# -_-V3.net
KiCad netlist of a schematic drawn in Altium Designer
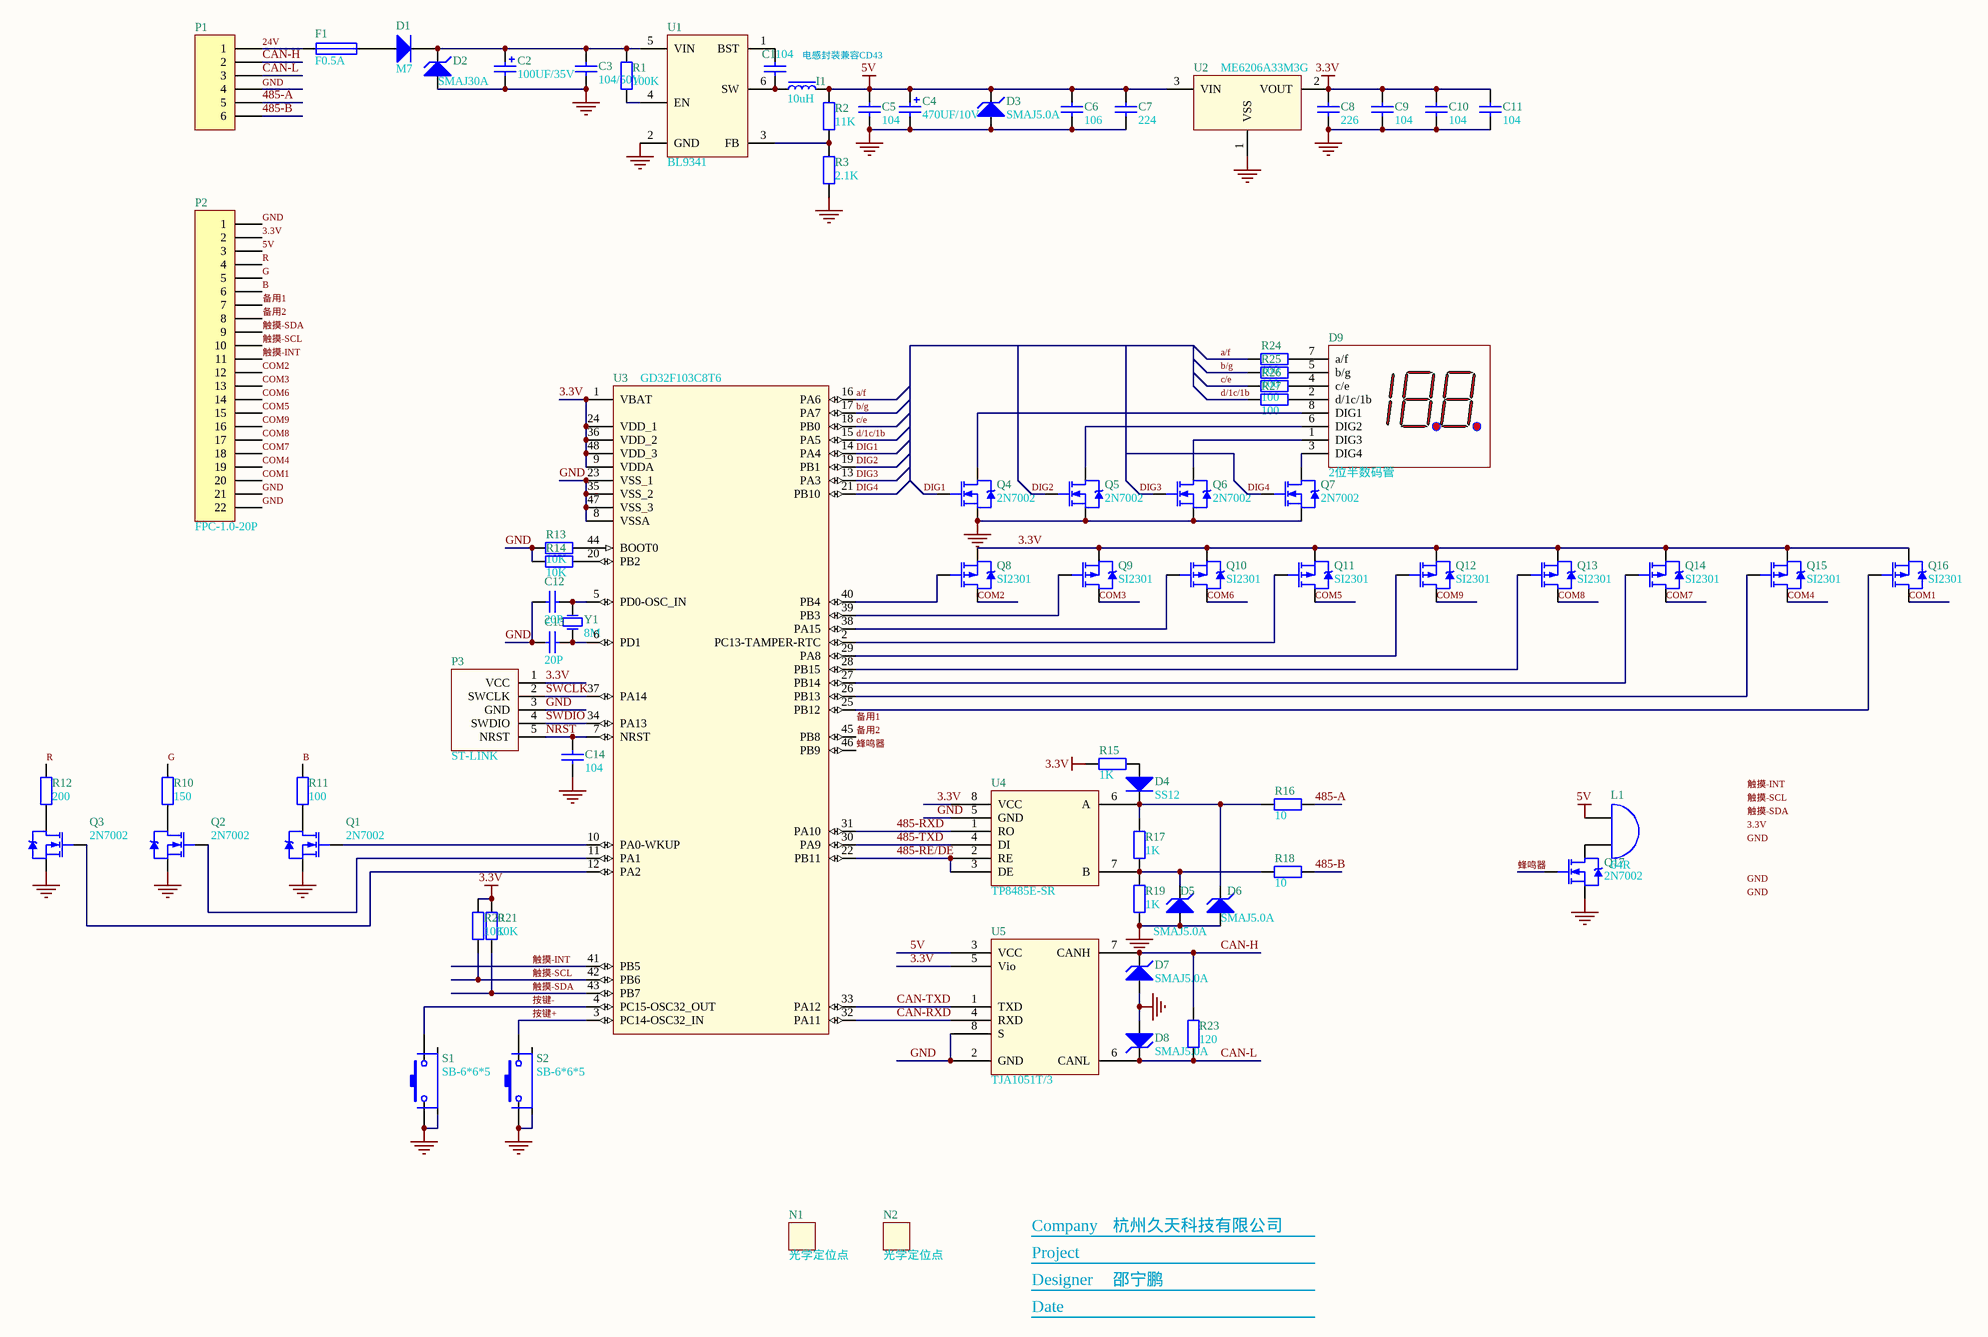
[diagram p0: 九键触摸面板-控制板-V3.SchDoc]

(export (version "E")
  (design (tool "Eeschema 10.0.6"))
  (components
    (comp (ref "C1")
      (value "104")
      (footprint "C-0603")
      (description "Capacitor")
      (fields (field (name "PUBLISHER") "Altium Limited"))
      (libsource (lib "元件2.0") (part "Cap"))
    )
    (comp (ref "C2")
      (value "100UF/35V")
      (footprint "贴片固态电容6.3*7.7")
      (description "Polarized Capacitor (Radial)")
      (fields (field (name "PUBLISHER") "Altium Limited"))
      (libsource (lib "元件2.0") (part "Cap Pol1"))
    )
    (comp (ref "C3")
      (value "104/50V")
      (footprint "C-0603")
      (description "Capacitor")
      (fields (field (name "PUBLISHER") "Altium Limited"))
      (libsource (lib "元件2.0") (part "Cap"))
    )
    (comp (ref "C4")
      (value "470UF/10V")
      (footprint "贴片固态电容6.3*7.7")
      (description "Polarized Capacitor (Radial)")
      (fields (field (name "PUBLISHER") "Altium Limited"))
      (libsource (lib "元件2.0") (part "Cap Pol1"))
    )
    (comp (ref "C5")
      (value "104")
      (footprint "C-0603")
      (description "Capacitor")
      (fields (field (name "PUBLISHER") "Altium Limited"))
      (libsource (lib "元件2.0") (part "Cap"))
    )
    (comp (ref "C6")
      (value "106")
      (footprint "C-0603")
      (description "Capacitor")
      (fields (field (name "PUBLISHER") "Altium Limited"))
      (libsource (lib "元件2.0") (part "Cap"))
    )
    (comp (ref "C7")
      (value "224")
      (footprint "C-0603")
      (description "Capacitor")
      (fields (field (name "PUBLISHER") "Altium Limited"))
      (libsource (lib "元件2.0") (part "Cap"))
    )
    (comp (ref "C8")
      (value "226")
      (footprint "C-0603")
      (description "Capacitor")
      (fields (field (name "PUBLISHER") "Altium Limited"))
      (libsource (lib "元件2.0") (part "Cap"))
    )
    (comp (ref "C9")
      (value "104")
      (footprint "C-0603")
      (description "Capacitor")
      (fields (field (name "PUBLISHER") "Altium Limited"))
      (libsource (lib "元件2.0") (part "Cap"))
    )
    (comp (ref "C10")
      (value "104")
      (footprint "C-0603")
      (description "Capacitor")
      (fields (field (name "PUBLISHER") "Altium Limited"))
      (libsource (lib "元件2.0") (part "Cap"))
    )
    (comp (ref "C11")
      (value "104")
      (footprint "C-0603")
      (description "Capacitor")
      (fields (field (name "PUBLISHER") "Altium Limited"))
      (libsource (lib "元件2.0") (part "Cap"))
    )
    (comp (ref "C12")
      (value "20P")
      (footprint "C-0603")
      (description "0805")
      (fields (field (name "PUBLISHER") "Altium Limited"))
      (libsource (lib "2电容-V1.0") (part "Cap-0603"))
    )
    (comp (ref "C13")
      (value "20P")
      (footprint "C-0603")
      (description "0805")
      (fields (field (name "PUBLISHER") "Altium Limited"))
      (libsource (lib "2电容-V1.0") (part "Cap-0603"))
    )
    (comp (ref "C14")
      (value "104")
      (footprint "C-0603")
      (description "0805")
      (fields (field (name "PUBLISHER") "Altium Limited"))
      (libsource (lib "2电容-V1.0") (part "Cap-0603"))
    )
    (comp (ref "D1")
      (value "M7")
      (footprint "SMA")
      (description "SMA")
      (fields (field (name "PUBLISHER") "Altium Limited"))
      (libsource (lib "4二极管-V1.1") (part "M7"))
    )
    (comp (ref "D2")
      (value "SMAJ30A")
      (footprint "SMA")
      (description "SMB")
      (libsource (lib "4二极管-V1.1") (part "TVS-1"))
    )
    (comp (ref "D3")
      (value "SMAJ5.0A")
      (footprint "SMA")
      (description "SMB")
      (libsource (lib "4二极管-V1.1") (part "TVS-1"))
    )
    (comp (ref "D4")
      (value "SS12")
      (footprint "SOD-323/0805")
      (description "SMA")
      (libsource (lib "4二极管-V1.1") (part "SS14"))
    )
    (comp (ref "D5")
      (value "SMAJ5.0A")
      (footprint "SMA")
      (description "SMB")
      (libsource (lib "4二极管-V1.1") (part "TVS-1"))
    )
    (comp (ref "D6")
      (value "SMAJ5.0A")
      (footprint "SMA")
      (description "SMB")
      (libsource (lib "4二极管-V1.1") (part "TVS-1"))
    )
    (comp (ref "D7")
      (value "SMAJ5.0A")
      (footprint "SMA")
      (description "SMB")
      (libsource (lib "4二极管-V1.1") (part "TVS-1"))
    )
    (comp (ref "D8")
      (value "SMAJ5.0A")
      (footprint "SMA")
      (description "SMB")
      (libsource (lib "4二极管-V1.1") (part "TVS-1"))
    )
    (comp (ref "D9") (value "2位半数码管") (footprint "2位半0.25英寸") (libsource (lib "7显示屏-V1.0") (part "2位半数码管")))
    (comp (ref "F1")
      (value "F0.5A")
      (footprint "FUSE-3*10带引线")
      (description "Fuse")
      (fields (field (name "PUBLISHER") "Altium Limited"))
      (libsource (lib "11其他元件-V1.0") (part "Fuse 1"))
    )
    (comp (ref "I1") (value "10uH") (footprint "4030") (libsource (lib "3电感-V1.0") (part "Inductance3")))
    (comp (ref "L1")
      (value "64R")
      (footprint "蜂鸣器 无源 12*8.2")
      (description "Electrical Bell")
      (fields (field (name "PUBLISHER") "Altium Limited"))
      (libsource (lib "11其他元件-V1.0") (part "Bell"))
    )
    (comp (ref "N1") (value "光学定位点") (footprint "MARK-1mm-3mm") (libsource (lib "11其他元件-V1.0") (part "无引脚")))
    (comp (ref "N2") (value "光学定位点") (footprint "MARK-1mm-3mm") (libsource (lib "11其他元件-V1.0") (part "无引脚")))
    (comp (ref "P1")
      (value "~")
      (footprint "KF2EDG-3.81-6P")
      (description "Header, 6-Pin")
      (fields (field (name "PUBLISHER") "Altium Limited"))
      (libsource (lib "5排针-V1.0") (part "Header 6"))
    )
    (comp (ref "P2")
      (value "FPC-1.0-20P")
      (footprint "FPC-1.0mm_20P下接翻盖")
      (description "Header, 22-Pin")
      (fields (field (name "PUBLISHER") "Altium Limited"))
      (libsource (lib "5排针-V1.0") (part "Header 22"))
    )
    (comp (ref "P3") (value "ST-LINK") (footprint "5P下载口") (libsource (lib "下载口") (part "ST-LINK-STM32")))
    (comp (ref "Q1") (value "2N7002") (footprint "SOT-23") (libsource (lib "4二极管-V1.1") (part "2N7002")))
    (comp (ref "Q2") (value "2N7002") (footprint "SOT-23") (libsource (lib "4二极管-V1.1") (part "2N7002")))
    (comp (ref "Q3") (value "2N7002") (footprint "SOT-23") (libsource (lib "4二极管-V1.1") (part "2N7002")))
    (comp (ref "Q4") (value "2N7002") (footprint "SOT-23") (libsource (lib "4二极管-V1.1") (part "2N7002")))
    (comp (ref "Q5") (value "2N7002") (footprint "SOT-23") (libsource (lib "4二极管-V1.1") (part "2N7002")))
    (comp (ref "Q6") (value "2N7002") (footprint "SOT-23") (libsource (lib "4二极管-V1.1") (part "2N7002")))
    (comp (ref "Q7") (value "2N7002") (footprint "SOT-23") (libsource (lib "4二极管-V1.1") (part "2N7002")))
    (comp (ref "Q8")
      (value "SI2301")
      (footprint "SOT-23")
      (description "SOT-23")
      (libsource (lib "4二极管-V1.1") (part "SI2301"))
    )
    (comp (ref "Q9")
      (value "SI2301")
      (footprint "SOT-23")
      (description "SOT-23")
      (libsource (lib "4二极管-V1.1") (part "SI2301"))
    )
    (comp (ref "Q10")
      (value "SI2301")
      (footprint "SOT-23")
      (description "SOT-23")
      (libsource (lib "4二极管-V1.1") (part "SI2301"))
    )
    (comp (ref "Q11")
      (value "SI2301")
      (footprint "SOT-23")
      (description "SOT-23")
      (libsource (lib "4二极管-V1.1") (part "SI2301"))
    )
    (comp (ref "Q12")
      (value "SI2301")
      (footprint "SOT-23")
      (description "SOT-23")
      (libsource (lib "4二极管-V1.1") (part "SI2301"))
    )
    (comp (ref "Q13")
      (value "SI2301")
      (footprint "SOT-23")
      (description "SOT-23")
      (libsource (lib "4二极管-V1.1") (part "SI2301"))
    )
    (comp (ref "Q14")
      (value "SI2301")
      (footprint "SOT-23")
      (description "SOT-23")
      (libsource (lib "4二极管-V1.1") (part "SI2301"))
    )
    (comp (ref "Q15")
      (value "SI2301")
      (footprint "SOT-23")
      (description "SOT-23")
      (libsource (lib "4二极管-V1.1") (part "SI2301"))
    )
    (comp (ref "Q16")
      (value "SI2301")
      (footprint "SOT-23")
      (description "SOT-23")
      (libsource (lib "4二极管-V1.1") (part "SI2301"))
    )
    (comp (ref "Q17") (value "2N7002") (footprint "SOT-23") (libsource (lib "4二极管-V1.1") (part "2N7002")))
    (comp (ref "R1")
      (value "100K")
      (footprint "R-0603")
      (description "0603")
      (fields (field (name "PUBLISHER") "Altium Limited"))
      (libsource (lib "1电阻-V1.0") (part "Res2-0603"))
    )
    (comp (ref "R2")
      (value "11K")
      (footprint "R-0603")
      (description "0603")
      (fields (field (name "PUBLISHER") "Altium Limited"))
      (libsource (lib "1电阻-V1.0") (part "Res2-0603"))
    )
    (comp (ref "R3")
      (value "2.1K")
      (footprint "R-0603")
      (description "0603")
      (fields (field (name "PUBLISHER") "Altium Limited"))
      (libsource (lib "1电阻-V1.0") (part "Res2-0603"))
    )
    (comp (ref "R10")
      (value "150")
      (footprint "R-0603")
      (description "0603")
      (fields (field (name "PUBLISHER") "Altium Limited"))
      (libsource (lib "") (part "Res2-0603_1"))
    )
    (comp (ref "R11")
      (value "100")
      (footprint "R-0603")
      (description "0603")
      (fields (field (name "PUBLISHER") "Altium Limited"))
      (libsource (lib "") (part "Res2-0603_1"))
    )
    (comp (ref "R12")
      (value "200")
      (footprint "R-0603")
      (description "0603")
      (fields (field (name "PUBLISHER") "Altium Limited"))
      (libsource (lib "") (part "Res2-0603_1"))
    )
    (comp (ref "R13")
      (value "10K")
      (footprint "R-0603")
      (description "0603")
      (fields (field (name "PUBLISHER") "Altium Limited"))
      (libsource (lib "1电阻-V1.0") (part "Res2-0603"))
    )
    (comp (ref "R14")
      (value "10K")
      (footprint "R-0603")
      (description "0603")
      (fields (field (name "PUBLISHER") "Altium Limited"))
      (libsource (lib "1电阻-V1.0") (part "Res2-0603"))
    )
    (comp (ref "R15")
      (value "1K")
      (footprint "R-0603")
      (description "Resistor")
      (fields (field (name "PUBLISHER") "Altium Limited"))
      (libsource (lib "元件2.0") (part "Res2"))
    )
    (comp (ref "R16")
      (value "10")
      (footprint "R-0603")
      (description "Resistor")
      (fields (field (name "PUBLISHER") "Altium Limited"))
      (libsource (lib "") (part "Res2_1"))
    )
    (comp (ref "R17")
      (value "1K")
      (footprint "R-1206")
      (description "Resistor")
      (fields (field (name "PUBLISHER") "Altium Limited"))
      (libsource (lib "Miscellaneous Devices") (part "Res2"))
    )
    (comp (ref "R18")
      (value "10")
      (footprint "R-0603")
      (description "Resistor")
      (fields (field (name "PUBLISHER") "Altium Limited"))
      (libsource (lib "") (part "Res2_1"))
    )
    (comp (ref "R19")
      (value "1K")
      (footprint "R-0603")
      (description "Resistor")
      (fields (field (name "PUBLISHER") "Altium Limited"))
      (libsource (lib "") (part "Res2_1"))
    )
    (comp (ref "R20")
      (value "10K")
      (footprint "R-0603")
      (description "0603")
      (fields (field (name "PUBLISHER") "Altium Limited"))
      (libsource (lib "") (part "Res2-0603_2"))
    )
    (comp (ref "R21")
      (value "10K")
      (footprint "R-0603")
      (description "0603")
      (fields (field (name "PUBLISHER") "Altium Limited"))
      (libsource (lib "") (part "Res2-0603_2"))
    )
    (comp (ref "R23")
      (value "120")
      (footprint "R-1206")
      (description "Resistor")
      (fields (field (name "PUBLISHER") "Altium Limited"))
      (libsource (lib "Miscellaneous Devices") (part "Res2"))
    )
    (comp (ref "R24")
      (value "100")
      (footprint "R-0603")
      (description "0603")
      (fields (field (name "PUBLISHER") "Altium Limited"))
      (libsource (lib "") (part "Res2-0603_2"))
    )
    (comp (ref "R25")
      (value "100")
      (footprint "R-0603")
      (description "0603")
      (fields (field (name "PUBLISHER") "Altium Limited"))
      (libsource (lib "") (part "Res2-0603_2"))
    )
    (comp (ref "R26")
      (value "100")
      (footprint "R-0603")
      (description "0603")
      (fields (field (name "PUBLISHER") "Altium Limited"))
      (libsource (lib "") (part "Res2-0603_2"))
    )
    (comp (ref "R27")
      (value "100")
      (footprint "R-0603")
      (description "0603")
      (fields (field (name "PUBLISHER") "Altium Limited"))
      (libsource (lib "") (part "Res2-0603_2"))
    )
    (comp (ref "S1")
      (value "SB-6*6*5")
      (footprint "SB-4.5*4.5*9")
      (fields (field (name "PUBLISHER") "Altium Limited"))
      (libsource (lib "开关-V1") (part "SB-6*6*5"))
    )
    (comp (ref "S2")
      (value "SB-6*6*5")
      (footprint "SB-4.5*4.5*9")
      (fields (field (name "PUBLISHER") "Altium Limited"))
      (libsource (lib "开关-V1") (part "SB-6*6*5"))
    )
    (comp (ref "U1") (value "BL9341") (footprint "SOT-23-6-m") (libsource (lib "电源芯片DC-DC") (part "BL9341")))
    (comp (ref "U2")
      (value "ME6206A33M3G")
      (footprint "SOT-23")
      (description "LDO稳压 SOT-23")
      (libsource (lib "电源芯片-线性稳压-V1") (part "ME6206A33M3G"))
    )
    (comp (ref "U3")
      (value "GD32F103C8T6")
      (footprint "LQFP48-L")
      (libsource (lib "9单片机-V1.0") (part "GD32F103C8T6"))
    )
    (comp (ref "U4")
      (value "TP8485E-SR")
      (footprint "SOP-8-m")
      (description "RS485总线转串口")
      (libsource (lib "集成电路1.0") (part "MAX3082"))
    )
    (comp (ref "U5") (value "TJA1051T/3") (footprint "SOP-8-M") (libsource (lib "通讯-V1") (part "TJA1051T/3")))
    (comp (ref "Y1") (value "8M") (footprint "HC-49SMD") (libsource (lib "11其他元件-V1.0") (part "晶振")))
  )
  (nets
    (net (code "1") (name "/24V") (class "Default")
      (node (ref "F1") (pin "1") (pinfunction "1_1") (pintype "passive"))
      (node (ref "P1") (pin "1") (pinfunction "1_1") (pintype "passive"))
    )
    (net (code "2") (name "/485-A") (class "Default")
      (node (ref "P1") (pin "5") (pinfunction "5_5") (pintype "passive"))
      (node (ref "R16") (pin "1") (pinfunction "1_1") (pintype "passive"))
    )
    (net (code "3") (name "/485-B") (class "Default")
      (node (ref "P1") (pin "6") (pinfunction "6_6") (pintype "passive"))
      (node (ref "R18") (pin "1") (pinfunction "1_1") (pintype "passive"))
    )
    (net (code "4") (name "/485-RE{slash}DE") (class "Default")
      (node (ref "U3") (pin "22") (pinfunction "PB11_22") (pintype "bidirectional"))
      (node (ref "U4") (pin "2") (pinfunction "RE_2") (pintype "passive"))
      (node (ref "U4") (pin "3") (pinfunction "DE_3") (pintype "passive"))
    )
    (net (code "5") (name "/485-RXD") (class "Default")
      (node (ref "U3") (pin "31") (pinfunction "PA10_31") (pintype "bidirectional"))
      (node (ref "U4") (pin "1") (pinfunction "RO_1") (pintype "passive"))
    )
    (net (code "6") (name "/485-TXD") (class "Default")
      (node (ref "U3") (pin "30") (pinfunction "PA9_30") (pintype "bidirectional"))
      (node (ref "U4") (pin "4") (pinfunction "DI_4") (pintype "passive"))
    )
    (net (code "7") (name "/B") (class "Default")
      (node (ref "P2") (pin "6") (pinfunction "6_6") (pintype "passive"))
      (node (ref "R11") (pin "2") (pinfunction "2_2") (pintype "passive"))
    )
    (net (code "8") (name "/CAN-H") (class "Default")
      (node (ref "D7") (pin "2") (pinfunction "K_2") (pintype "passive"))
      (node (ref "P1") (pin "2") (pinfunction "2_2") (pintype "passive"))
      (node (ref "R23") (pin "1") (pinfunction "1_1") (pintype "passive"))
      (node (ref "U5") (pin "7") (pinfunction "CANH_7") (pintype "passive"))
    )
    (net (code "9") (name "/CAN-L") (class "Default")
      (node (ref "D8") (pin "2") (pinfunction "K_2") (pintype "passive"))
      (node (ref "P1") (pin "3") (pinfunction "3_3") (pintype "passive"))
      (node (ref "R23") (pin "2") (pinfunction "2_2") (pintype "passive"))
      (node (ref "U5") (pin "6") (pinfunction "CANL_6") (pintype "passive"))
    )
    (net (code "10") (name "/CAN-RXD") (class "Default")
      (node (ref "U3") (pin "32") (pinfunction "PA11_32") (pintype "bidirectional"))
      (node (ref "U5") (pin "4") (pinfunction "RXD_4") (pintype "passive"))
    )
    (net (code "11") (name "/CAN-TXD") (class "Default")
      (node (ref "U3") (pin "33") (pinfunction "PA12_33") (pintype "bidirectional"))
      (node (ref "U5") (pin "1") (pinfunction "TXD_1") (pintype "passive"))
    )
    (net (code "12") (name "/COM1") (class "Default")
      (node (ref "P2") (pin "20") (pinfunction "20_20") (pintype "passive"))
      (node (ref "Q16") (pin "3") (pinfunction "D_3") (pintype "passive"))
    )
    (net (code "13") (name "/COM2") (class "Default")
      (node (ref "P2") (pin "12") (pinfunction "12_12") (pintype "passive"))
      (node (ref "Q8") (pin "3") (pinfunction "D_3") (pintype "passive"))
    )
    (net (code "14") (name "/COM3") (class "Default")
      (node (ref "P2") (pin "13") (pinfunction "13_13") (pintype "passive"))
      (node (ref "Q9") (pin "3") (pinfunction "D_3") (pintype "passive"))
    )
    (net (code "15") (name "/COM4") (class "Default")
      (node (ref "P2") (pin "19") (pinfunction "19_19") (pintype "passive"))
      (node (ref "Q15") (pin "3") (pinfunction "D_3") (pintype "passive"))
    )
    (net (code "16") (name "/COM5") (class "Default")
      (node (ref "P2") (pin "15") (pinfunction "15_15") (pintype "passive"))
      (node (ref "Q11") (pin "3") (pinfunction "D_3") (pintype "passive"))
    )
    (net (code "17") (name "/COM6") (class "Default")
      (node (ref "P2") (pin "14") (pinfunction "14_14") (pintype "passive"))
      (node (ref "Q10") (pin "3") (pinfunction "D_3") (pintype "passive"))
    )
    (net (code "18") (name "/COM7") (class "Default")
      (node (ref "P2") (pin "18") (pinfunction "18_18") (pintype "passive"))
      (node (ref "Q14") (pin "3") (pinfunction "D_3") (pintype "passive"))
    )
    (net (code "19") (name "/COM8") (class "Default")
      (node (ref "P2") (pin "17") (pinfunction "17_17") (pintype "passive"))
      (node (ref "Q13") (pin "3") (pinfunction "D_3") (pintype "passive"))
    )
    (net (code "20") (name "/COM9") (class "Default")
      (node (ref "P2") (pin "16") (pinfunction "16_16") (pintype "passive"))
      (node (ref "Q12") (pin "3") (pinfunction "D_3") (pintype "passive"))
    )
    (net (code "21") (name "/DIG1") (class "Default")
      (node (ref "Q4") (pin "1") (pinfunction "G_1") (pintype "passive"))
      (node (ref "U3") (pin "14") (pinfunction "PA4_14") (pintype "bidirectional"))
    )
    (net (code "22") (name "/DIG2") (class "Default")
      (node (ref "Q5") (pin "1") (pinfunction "G_1") (pintype "passive"))
      (node (ref "U3") (pin "19") (pinfunction "PB1_19") (pintype "bidirectional"))
    )
    (net (code "23") (name "/DIG3") (class "Default")
      (node (ref "Q6") (pin "1") (pinfunction "G_1") (pintype "passive"))
      (node (ref "U3") (pin "13") (pinfunction "PA3_13") (pintype "bidirectional"))
    )
    (net (code "24") (name "/DIG4") (class "Default")
      (node (ref "Q7") (pin "1") (pinfunction "G_1") (pintype "passive"))
      (node (ref "U3") (pin "21") (pinfunction "PB10_21") (pintype "bidirectional"))
    )
    (net (code "25") (name "/G") (class "Default")
      (node (ref "P2") (pin "5") (pinfunction "5_5") (pintype "passive"))
      (node (ref "R10") (pin "2") (pinfunction "2_2") (pintype "passive"))
    )
    (net (code "26") (name "/NRST") (class "Default")
      (node (ref "C14") (pin "2") (pinfunction "2_2") (pintype "passive"))
      (node (ref "P3") (pin "5") (pinfunction "NRST_5") (pintype "passive"))
      (node (ref "U3") (pin "7") (pinfunction "NRST_7") (pintype "bidirectional"))
    )
    (net (code "27") (name "/R") (class "Default")
      (node (ref "P2") (pin "4") (pinfunction "4_4") (pintype "passive"))
      (node (ref "R12") (pin "2") (pinfunction "2_2") (pintype "passive"))
    )
    (net (code "28") (name "/SWCLK") (class "Default")
      (node (ref "P3") (pin "2") (pinfunction "SWCLK_2") (pintype "passive"))
      (node (ref "U3") (pin "37") (pinfunction "PA14_37") (pintype "bidirectional"))
    )
    (net (code "29") (name "/SWDIO") (class "Default")
      (node (ref "P3") (pin "4") (pinfunction "SWDIO_4") (pintype "passive"))
      (node (ref "U3") (pin "34") (pinfunction "PA13_34") (pintype "bidirectional"))
    )
    (net (code "30") (name "/a{slash}f") (class "Default")
      (node (ref "R24") (pin "1") (pinfunction "1_1") (pintype "passive"))
      (node (ref "U3") (pin "16") (pinfunction "PA6_16") (pintype "bidirectional"))
    )
    (net (code "31") (name "/b{slash}g") (class "Default")
      (node (ref "R25") (pin "1") (pinfunction "1_1") (pintype "passive"))
      (node (ref "U3") (pin "17") (pinfunction "PA7_17") (pintype "bidirectional"))
    )
    (net (code "32") (name "/c{slash}e") (class "Default")
      (node (ref "R26") (pin "1") (pinfunction "1_1") (pintype "passive"))
      (node (ref "U3") (pin "18") (pinfunction "PB0_18") (pintype "bidirectional"))
    )
    (net (code "33") (name "/d{slash}1c{slash}1b") (class "Default")
      (node (ref "R27") (pin "1") (pinfunction "1_1") (pintype "passive"))
      (node (ref "U3") (pin "15") (pinfunction "PA5_15") (pintype "bidirectional"))
    )
    (net (code "34") (name "/备用1") (class "Default")
      (node (ref "P2") (pin "7") (pinfunction "7_7") (pintype "passive"))
    )
    (net (code "35") (name "/备用2") (class "Default")
      (node (ref "P2") (pin "8") (pinfunction "8_8") (pintype "passive"))
      (node (ref "U3") (pin "45") (pinfunction "PB8_45") (pintype "bidirectional"))
    )
    (net (code "36") (name "/按键+") (class "Default")
      (node (ref "S2") (pin "1") (pinfunction "1_1") (pintype "passive"))
      (node (ref "U3") (pin "3") (pinfunction "PC14-OSC32_IN_3") (pintype "bidirectional"))
    )
    (net (code "37") (name "/按键-") (class "Default")
      (node (ref "S1") (pin "1") (pinfunction "1_1") (pintype "passive"))
      (node (ref "U3") (pin "4") (pinfunction "PC15-OSC32_OUT_4") (pintype "bidirectional"))
    )
    (net (code "38") (name "/蜂鸣器") (class "Default")
      (node (ref "Q17") (pin "1") (pinfunction "G_1") (pintype "passive"))
      (node (ref "U3") (pin "46") (pinfunction "PB9_46") (pintype "bidirectional"))
    )
    (net (code "39") (name "/触摸-INT") (class "Default")
      (node (ref "P2") (pin "11") (pinfunction "11_11") (pintype "passive"))
      (node (ref "U3") (pin "41") (pinfunction "PB5_41") (pintype "bidirectional"))
    )
    (net (code "40") (name "/触摸-SCL") (class "Default")
      (node (ref "P2") (pin "10") (pinfunction "10_10") (pintype "passive"))
      (node (ref "R20") (pin "1") (pinfunction "1_1") (pintype "passive"))
      (node (ref "U3") (pin "42") (pinfunction "PB6_42") (pintype "bidirectional"))
    )
    (net (code "41") (name "/触摸-SDA") (class "Default")
      (node (ref "P2") (pin "9") (pinfunction "9_9") (pintype "passive"))
      (node (ref "R21") (pin "1") (pinfunction "1_1") (pintype "passive"))
      (node (ref "U3") (pin "43") (pinfunction "PB7_43") (pintype "bidirectional"))
    )
    (net (code "42") (name "3.3V") (class "Default")
      (node (ref "C10") (pin "2") (pinfunction "2_2") (pintype "passive"))
      (node (ref "C11") (pin "2") (pinfunction "2_2") (pintype "passive"))
      (node (ref "C8") (pin "2") (pinfunction "2_2") (pintype "passive"))
      (node (ref "C9") (pin "2") (pinfunction "2_2") (pintype "passive"))
      (node (ref "P2") (pin "2") (pinfunction "2_2") (pintype "passive"))
      (node (ref "P3") (pin "1") (pinfunction "VCC_1") (pintype "passive"))
      (node (ref "Q10") (pin "2") (pinfunction "S_2") (pintype "passive"))
      (node (ref "Q11") (pin "2") (pinfunction "S_2") (pintype "passive"))
      (node (ref "Q12") (pin "2") (pinfunction "S_2") (pintype "passive"))
      (node (ref "Q13") (pin "2") (pinfunction "S_2") (pintype "passive"))
      (node (ref "Q14") (pin "2") (pinfunction "S_2") (pintype "passive"))
      (node (ref "Q15") (pin "2") (pinfunction "S_2") (pintype "passive"))
      (node (ref "Q16") (pin "2") (pinfunction "S_2") (pintype "passive"))
      (node (ref "Q8") (pin "2") (pinfunction "S_2") (pintype "passive"))
      (node (ref "Q9") (pin "2") (pinfunction "S_2") (pintype "passive"))
      (node (ref "R15") (pin "1") (pinfunction "1_1") (pintype "passive"))
      (node (ref "R20") (pin "2") (pinfunction "2_2") (pintype "passive"))
      (node (ref "R21") (pin "2") (pinfunction "2_2") (pintype "passive"))
      (node (ref "U2") (pin "2") (pinfunction "VOUT_2") (pintype "passive"))
      (node (ref "U3") (pin "1") (pinfunction "VBAT_1") (pintype "power_in"))
      (node (ref "U3") (pin "24") (pinfunction "VDD_1_24") (pintype "power_in"))
      (node (ref "U3") (pin "36") (pinfunction "VDD_2_36") (pintype "power_in"))
      (node (ref "U3") (pin "48") (pinfunction "VDD_3_48") (pintype "power_in"))
      (node (ref "U3") (pin "9") (pinfunction "VDDA_9") (pintype "power_in"))
      (node (ref "U4") (pin "8") (pinfunction "VCC_8") (pintype "passive"))
      (node (ref "U5") (pin "5") (pinfunction "Vio_5") (pintype "passive"))
    )
    (net (code "43") (name "5V") (class "Default")
      (node (ref "C4") (pin "1") (pinfunction "1_1") (pintype "passive"))
      (node (ref "C5") (pin "2") (pinfunction "2_2") (pintype "passive"))
      (node (ref "C6") (pin "2") (pinfunction "2_2") (pintype "passive"))
      (node (ref "C7") (pin "2") (pinfunction "2_2") (pintype "passive"))
      (node (ref "D3") (pin "2") (pinfunction "K_2") (pintype "passive"))
      (node (ref "I1") (pin "2") (pinfunction "2_2") (pintype "passive"))
      (node (ref "L1") (pin "1") (pinfunction "A_1") (pintype "passive"))
      (node (ref "P2") (pin "3") (pinfunction "3_3") (pintype "passive"))
      (node (ref "R2") (pin "1") (pinfunction "1_1") (pintype "passive"))
      (node (ref "U2") (pin "3") (pinfunction "VIN_3") (pintype "passive"))
      (node (ref "U5") (pin "3") (pinfunction "VCC_3") (pintype "passive"))
    )
    (net (code "44") (name "GND") (class "Default")
      (node (ref "C10") (pin "1") (pinfunction "1_1") (pintype "passive"))
      (node (ref "C11") (pin "1") (pinfunction "1_1") (pintype "passive"))
      (node (ref "C12") (pin "1") (pinfunction "1_1") (pintype "passive"))
      (node (ref "C13") (pin "1") (pinfunction "1_1") (pintype "passive"))
      (node (ref "C14") (pin "1") (pinfunction "1_1") (pintype "passive"))
      (node (ref "C2") (pin "2") (pinfunction "2_2") (pintype "passive"))
      (node (ref "C3") (pin "1") (pinfunction "1_1") (pintype "passive"))
      (node (ref "C4") (pin "2") (pinfunction "2_2") (pintype "passive"))
      (node (ref "C5") (pin "1") (pinfunction "1_1") (pintype "passive"))
      (node (ref "C6") (pin "1") (pinfunction "1_1") (pintype "passive"))
      (node (ref "C7") (pin "1") (pinfunction "1_1") (pintype "passive"))
      (node (ref "C8") (pin "1") (pinfunction "1_1") (pintype "passive"))
      (node (ref "C9") (pin "1") (pinfunction "1_1") (pintype "passive"))
      (node (ref "D2") (pin "1") (pinfunction "A_1") (pintype "passive"))
      (node (ref "D3") (pin "1") (pinfunction "A_1") (pintype "passive"))
      (node (ref "D5") (pin "1") (pinfunction "A_1") (pintype "passive"))
      (node (ref "D6") (pin "1") (pinfunction "A_1") (pintype "passive"))
      (node (ref "D7") (pin "1") (pinfunction "A_1") (pintype "passive"))
      (node (ref "D8") (pin "1") (pinfunction "A_1") (pintype "passive"))
      (node (ref "P1") (pin "4") (pinfunction "4_4") (pintype "passive"))
      (node (ref "P2") (pin "1") (pinfunction "1_1") (pintype "passive"))
      (node (ref "P2") (pin "21") (pinfunction "21_21") (pintype "passive"))
      (node (ref "P2") (pin "22") (pinfunction "22_22") (pintype "passive"))
      (node (ref "P3") (pin "3") (pinfunction "GND_3") (pintype "passive"))
      (node (ref "Q1") (pin "2") (pinfunction "S_2") (pintype "passive"))
      (node (ref "Q17") (pin "2") (pinfunction "S_2") (pintype "passive"))
      (node (ref "Q2") (pin "2") (pinfunction "S_2") (pintype "passive"))
      (node (ref "Q3") (pin "2") (pinfunction "S_2") (pintype "passive"))
      (node (ref "Q4") (pin "2") (pinfunction "S_2") (pintype "passive"))
      (node (ref "Q5") (pin "2") (pinfunction "S_2") (pintype "passive"))
      (node (ref "Q6") (pin "2") (pinfunction "S_2") (pintype "passive"))
      (node (ref "Q7") (pin "2") (pinfunction "S_2") (pintype "passive"))
      (node (ref "R13") (pin "2") (pinfunction "2_2") (pintype "passive"))
      (node (ref "R14") (pin "2") (pinfunction "2_2") (pintype "passive"))
      (node (ref "R19") (pin "1") (pinfunction "1_1") (pintype "passive"))
      (node (ref "R3") (pin "2") (pinfunction "2_2") (pintype "passive"))
      (node (ref "S1") (pin "2") (pinfunction "2_2") (pintype "passive"))
      (node (ref "S1") (pin "3") (pinfunction "3_3") (pintype "passive"))
      (node (ref "S2") (pin "2") (pinfunction "2_2") (pintype "passive"))
      (node (ref "S2") (pin "3") (pinfunction "3_3") (pintype "passive"))
      (node (ref "U1") (pin "2") (pinfunction "GND_2") (pintype "passive"))
      (node (ref "U2") (pin "1") (pinfunction "VSS_1") (pintype "passive"))
      (node (ref "U3") (pin "23") (pinfunction "VSS_1_23") (pintype "power_in"))
      (node (ref "U3") (pin "35") (pinfunction "VSS_2_35") (pintype "power_in"))
      (node (ref "U3") (pin "47") (pinfunction "VSS_3_47") (pintype "power_in"))
      (node (ref "U3") (pin "8") (pinfunction "VSSA_8") (pintype "power_in"))
      (node (ref "U4") (pin "5") (pinfunction "GND_5") (pintype "passive"))
      (node (ref "U5") (pin "2") (pinfunction "GND_2") (pintype "passive"))
      (node (ref "U5") (pin "8") (pinfunction "S_8") (pintype "passive"))
    )
    (net (code "45") (name "Net-(D1-A)") (class "Default")
      (node (ref "D1") (pin "1") (pinfunction "A_1") (pintype "passive"))
      (node (ref "F1") (pin "2") (pinfunction "2_2") (pintype "passive"))
    )
    (net (code "46") (name "Net-(D1-K)") (class "Default")
      (node (ref "C2") (pin "1") (pinfunction "1_1") (pintype "passive"))
      (node (ref "C3") (pin "2") (pinfunction "2_2") (pintype "passive"))
      (node (ref "D1") (pin "2") (pinfunction "K_2") (pintype "passive"))
      (node (ref "D2") (pin "2") (pinfunction "K_2") (pintype "passive"))
      (node (ref "R1") (pin "1") (pinfunction "1_1") (pintype "passive"))
      (node (ref "U1") (pin "5") (pinfunction "VIN_5") (pintype "passive"))
    )
    (net (code "47") (name "Net-(D4-A)") (class "Default")
      (node (ref "D4") (pin "1") (pinfunction "A_1") (pintype "passive"))
      (node (ref "R15") (pin "2") (pinfunction "2_2") (pintype "passive"))
    )
    (net (code "48") (name "Net-(D4-K)") (class "Default")
      (node (ref "D4") (pin "2") (pinfunction "K_2") (pintype "passive"))
      (node (ref "D6") (pin "2") (pinfunction "K_2") (pintype "passive"))
      (node (ref "R16") (pin "2") (pinfunction "2_2") (pintype "passive"))
      (node (ref "R17") (pin "1") (pinfunction "1_1") (pintype "passive"))
      (node (ref "U4") (pin "6") (pinfunction "A_6") (pintype "passive"))
    )
    (net (code "49") (name "Net-(D5-K)") (class "Default")
      (node (ref "D5") (pin "2") (pinfunction "K_2") (pintype "passive"))
      (node (ref "R17") (pin "2") (pinfunction "2_2") (pintype "passive"))
      (node (ref "R18") (pin "2") (pinfunction "2_2") (pintype "passive"))
      (node (ref "R19") (pin "2") (pinfunction "2_2") (pintype "passive"))
      (node (ref "U4") (pin "7") (pinfunction "B_7") (pintype "passive"))
    )
    (net (code "50") (name "Net-(D9-DIG1)") (class "Default")
      (node (ref "D9") (pin "8") (pinfunction "DIG1_8") (pintype "passive"))
      (node (ref "Q4") (pin "3") (pinfunction "D_3") (pintype "passive"))
    )
    (net (code "51") (name "Net-(D9-DIG2)") (class "Default")
      (node (ref "D9") (pin "6") (pinfunction "DIG2_6") (pintype "passive"))
      (node (ref "Q5") (pin "3") (pinfunction "D_3") (pintype "passive"))
    )
    (net (code "52") (name "Net-(D9-DIG3)") (class "Default")
      (node (ref "D9") (pin "1") (pinfunction "DIG3_1") (pintype "passive"))
      (node (ref "Q6") (pin "3") (pinfunction "D_3") (pintype "passive"))
    )
    (net (code "53") (name "Net-(D9-DIG4)") (class "Default")
      (node (ref "D9") (pin "3") (pinfunction "DIG4_3") (pintype "passive"))
      (node (ref "Q7") (pin "3") (pinfunction "D_3") (pintype "passive"))
    )
    (net (code "54") (name "Net-(D9-a{slash}f)") (class "Default")
      (node (ref "D9") (pin "7") (pinfunction "a/f_7") (pintype "passive"))
      (node (ref "R24") (pin "2") (pinfunction "2_2") (pintype "passive"))
    )
    (net (code "55") (name "Net-(D9-b{slash}g)") (class "Default")
      (node (ref "D9") (pin "5") (pinfunction "b/g_5") (pintype "passive"))
      (node (ref "R25") (pin "2") (pinfunction "2_2") (pintype "passive"))
    )
    (net (code "56") (name "Net-(D9-c{slash}e)") (class "Default")
      (node (ref "D9") (pin "4") (pinfunction "c/e_4") (pintype "passive"))
      (node (ref "R26") (pin "2") (pinfunction "2_2") (pintype "passive"))
    )
    (net (code "57") (name "Net-(D9-d{slash}1c{slash}1b)") (class "Default")
      (node (ref "D9") (pin "2") (pinfunction "d/1c/1b_2") (pintype "passive"))
      (node (ref "R27") (pin "2") (pinfunction "2_2") (pintype "passive"))
    )
    (net (code "58") (name "Net-(L1-B)") (class "Default")
      (node (ref "L1") (pin "2") (pinfunction "B_2") (pintype "passive"))
      (node (ref "Q17") (pin "3") (pinfunction "D_3") (pintype "passive"))
    )
    (net (code "59") (name "Net-(Q1-D)") (class "Default")
      (node (ref "Q1") (pin "3") (pinfunction "D_3") (pintype "passive"))
      (node (ref "R11") (pin "1") (pinfunction "1_1") (pintype "passive"))
    )
    (net (code "60") (name "Net-(Q1-G)") (class "Default")
      (node (ref "Q1") (pin "1") (pinfunction "G_1") (pintype "passive"))
      (node (ref "U3") (pin "10") (pinfunction "PA0-WKUP_10") (pintype "bidirectional"))
    )
    (net (code "61") (name "Net-(Q2-D)") (class "Default")
      (node (ref "Q2") (pin "3") (pinfunction "D_3") (pintype "passive"))
      (node (ref "R10") (pin "1") (pinfunction "1_1") (pintype "passive"))
    )
    (net (code "62") (name "Net-(Q2-G)") (class "Default")
      (node (ref "Q2") (pin "1") (pinfunction "G_1") (pintype "passive"))
      (node (ref "U3") (pin "11") (pinfunction "PA1_11") (pintype "bidirectional"))
    )
    (net (code "63") (name "Net-(Q3-D)") (class "Default")
      (node (ref "Q3") (pin "3") (pinfunction "D_3") (pintype "passive"))
      (node (ref "R12") (pin "1") (pinfunction "1_1") (pintype "passive"))
    )
    (net (code "64") (name "Net-(Q3-G)") (class "Default")
      (node (ref "Q3") (pin "1") (pinfunction "G_1") (pintype "passive"))
      (node (ref "U3") (pin "12") (pinfunction "PA2_12") (pintype "bidirectional"))
    )
    (net (code "65") (name "Net-(Q8-G)") (class "Default")
      (node (ref "Q8") (pin "1") (pinfunction "G_1") (pintype "passive"))
      (node (ref "U3") (pin "40") (pinfunction "PB4_40") (pintype "bidirectional"))
    )
    (net (code "66") (name "Net-(Q9-G)") (class "Default")
      (node (ref "Q9") (pin "1") (pinfunction "G_1") (pintype "passive"))
      (node (ref "U3") (pin "39") (pinfunction "PB3_39") (pintype "bidirectional"))
    )
    (net (code "67") (name "Net-(Q10-G)") (class "Default")
      (node (ref "Q10") (pin "1") (pinfunction "G_1") (pintype "passive"))
      (node (ref "U3") (pin "38") (pinfunction "PA15_38") (pintype "bidirectional"))
    )
    (net (code "68") (name "Net-(Q11-G)") (class "Default")
      (node (ref "Q11") (pin "1") (pinfunction "G_1") (pintype "passive"))
      (node (ref "U3") (pin "2") (pinfunction "PC13-TAMPER-RTC_2") (pintype "bidirectional"))
    )
    (net (code "69") (name "Net-(Q12-G)") (class "Default")
      (node (ref "Q12") (pin "1") (pinfunction "G_1") (pintype "passive"))
      (node (ref "U3") (pin "29") (pinfunction "PA8_29") (pintype "bidirectional"))
    )
    (net (code "70") (name "Net-(Q13-G)") (class "Default")
      (node (ref "Q13") (pin "1") (pinfunction "G_1") (pintype "passive"))
      (node (ref "U3") (pin "28") (pinfunction "PB15_28") (pintype "bidirectional"))
    )
    (net (code "71") (name "Net-(Q14-G)") (class "Default")
      (node (ref "Q14") (pin "1") (pinfunction "G_1") (pintype "passive"))
      (node (ref "U3") (pin "27") (pinfunction "PB14_27") (pintype "bidirectional"))
    )
    (net (code "72") (name "Net-(Q15-G)") (class "Default")
      (node (ref "Q15") (pin "1") (pinfunction "G_1") (pintype "passive"))
      (node (ref "U3") (pin "26") (pinfunction "PB13_26") (pintype "bidirectional"))
    )
    (net (code "73") (name "Net-(Q16-G)") (class "Default")
      (node (ref "Q16") (pin "1") (pinfunction "G_1") (pintype "passive"))
      (node (ref "U3") (pin "25") (pinfunction "PB12_25") (pintype "bidirectional"))
    )
    (net (code "74") (name "Net-(U1-BST)") (class "Default")
      (node (ref "C1") (pin "2") (pinfunction "2_2") (pintype "passive"))
      (node (ref "U1") (pin "1") (pinfunction "BST_1") (pintype "passive"))
    )
    (net (code "75") (name "Net-(U1-EN)") (class "Default")
      (node (ref "R1") (pin "2") (pinfunction "2_2") (pintype "passive"))
      (node (ref "U1") (pin "4") (pinfunction "EN_4") (pintype "passive"))
    )
    (net (code "76") (name "Net-(U1-FB)") (class "Default")
      (node (ref "R2") (pin "2") (pinfunction "2_2") (pintype "passive"))
      (node (ref "R3") (pin "1") (pinfunction "1_1") (pintype "passive"))
      (node (ref "U1") (pin "3") (pinfunction "FB_3") (pintype "passive"))
    )
    (net (code "77") (name "Net-(U1-SW)") (class "Default")
      (node (ref "C1") (pin "1") (pinfunction "1_1") (pintype "passive"))
      (node (ref "I1") (pin "1") (pinfunction "1_1") (pintype "passive"))
      (node (ref "U1") (pin "6") (pinfunction "SW_6") (pintype "passive"))
    )
    (net (code "78") (name "Net-(U3-BOOT0)") (class "Default")
      (node (ref "R13") (pin "1") (pinfunction "1_1") (pintype "passive"))
      (node (ref "U3") (pin "44") (pinfunction "BOOT0_44") (pintype "input"))
    )
    (net (code "79") (name "Net-(U3-PB2)") (class "Default")
      (node (ref "R14") (pin "1") (pinfunction "1_1") (pintype "passive"))
      (node (ref "U3") (pin "20") (pinfunction "PB2_20") (pintype "bidirectional"))
    )
    (net (code "80") (name "Net-(U3-PD0-OSC_IN)") (class "Default")
      (node (ref "C12") (pin "2") (pinfunction "2_2") (pintype "passive"))
      (node (ref "U3") (pin "5") (pinfunction "PD0-OSC_IN_5") (pintype "bidirectional"))
      (node (ref "Y1") (pin "2") (pinfunction "OSC2_2") (pintype "passive"))
    )
    (net (code "81") (name "Net-(U3-PD1)") (class "Default")
      (node (ref "C13") (pin "2") (pinfunction "2_2") (pintype "passive"))
      (node (ref "U3") (pin "6") (pinfunction "PD1_6") (pintype "bidirectional"))
      (node (ref "Y1") (pin "1") (pinfunction "OSC1_1") (pintype "passive"))
    )
    (net (code "82") (name "unconnected-(S1-Pad3)") (class "Default")
      (node (ref "S1") (pin "3") (pinfunction "3_3") (pintype "passive"))
    )
    (net (code "83") (name "unconnected-(S2-Pad3)") (class "Default")
      (node (ref "S2") (pin "3") (pinfunction "3_3") (pintype "passive"))
    )
  )
)
